# CONNECTOR.net
KiCad netlist of a schematic drawn in Altium Designer
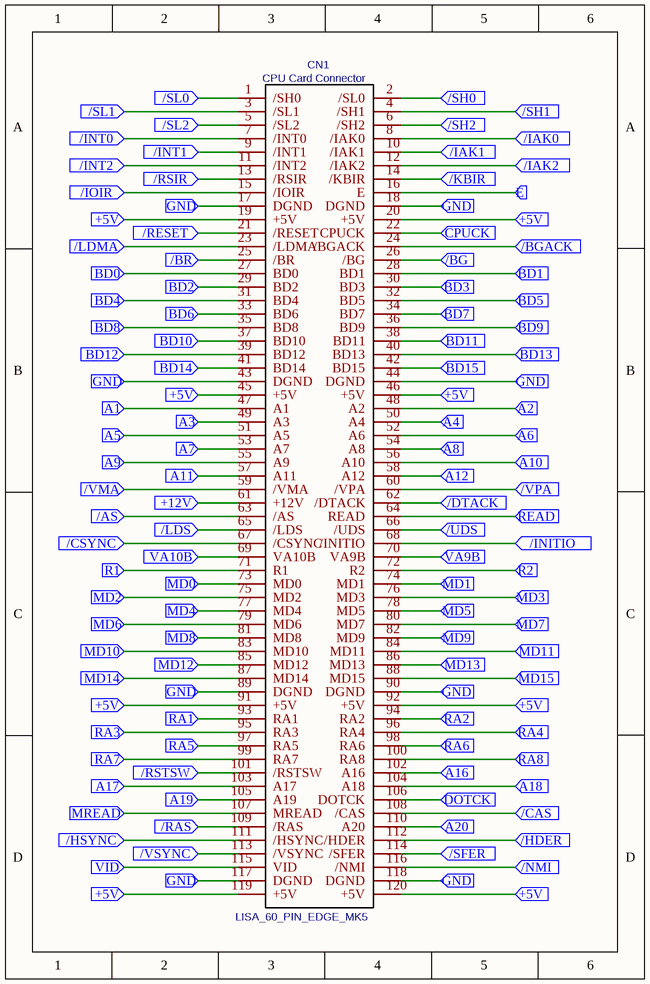
[diagram p0: CONNECTOR.schdoc]

(export (version "E")
  (design (tool "Eeschema 10.0.6"))
  (components
    (comp (ref "CN1")
      (value "CPU Card Connector")
      (fields (field (name "CONTRIBUTOR") "will_tooker"))
      (libsource (lib "altium-import") (part "root_0_CPU Card Connector_"))
    )
  )
  (nets
    (net (code "1") (name "/+5V") (class "Default")
      (node (ref "CN1") (pin "119") (pinfunction "+5V_119") (pintype "passive"))
      (node (ref "CN1") (pin "120") (pinfunction "+5V_120") (pintype "passive"))
      (node (ref "CN1") (pin "19") (pinfunction "+5V_19") (pintype "passive"))
      (node (ref "CN1") (pin "20") (pinfunction "+5V_20") (pintype "passive"))
      (node (ref "CN1") (pin "45") (pinfunction "+5V_45") (pintype "passive"))
      (node (ref "CN1") (pin "46") (pinfunction "+5V_46") (pintype "passive"))
      (node (ref "CN1") (pin "91") (pinfunction "+5V_91") (pintype "passive"))
      (node (ref "CN1") (pin "92") (pinfunction "+5V_92") (pintype "passive"))
    )
    (net (code "2") (name "/+12V") (class "Default")
      (node (ref "CN1") (pin "61") (pinfunction "+12V_61") (pintype "passive"))
    )
    (net (code "3") (name "/A1") (class "Default")
      (node (ref "CN1") (pin "47") (pinfunction "A1_47") (pintype "passive"))
    )
    (net (code "4") (name "/A2") (class "Default")
      (node (ref "CN1") (pin "48") (pinfunction "A2_48") (pintype "passive"))
    )
    (net (code "5") (name "/A3") (class "Default")
      (node (ref "CN1") (pin "49") (pinfunction "A3_49") (pintype "passive"))
    )
    (net (code "6") (name "/A4") (class "Default")
      (node (ref "CN1") (pin "50") (pinfunction "A4_50") (pintype "passive"))
    )
    (net (code "7") (name "/A5") (class "Default")
      (node (ref "CN1") (pin "51") (pinfunction "A5_51") (pintype "passive"))
    )
    (net (code "8") (name "/A6") (class "Default")
      (node (ref "CN1") (pin "52") (pinfunction "A6_52") (pintype "passive"))
    )
    (net (code "9") (name "/A7") (class "Default")
      (node (ref "CN1") (pin "53") (pinfunction "A7_53") (pintype "passive"))
    )
    (net (code "10") (name "/A8") (class "Default")
      (node (ref "CN1") (pin "54") (pinfunction "A8_54") (pintype "passive"))
    )
    (net (code "11") (name "/A9") (class "Default")
      (node (ref "CN1") (pin "55") (pinfunction "A9_55") (pintype "passive"))
    )
    (net (code "12") (name "/A10") (class "Default")
      (node (ref "CN1") (pin "56") (pinfunction "A10_56") (pintype "passive"))
    )
    (net (code "13") (name "/A11") (class "Default")
      (node (ref "CN1") (pin "57") (pinfunction "A11_57") (pintype "passive"))
    )
    (net (code "14") (name "/A12") (class "Default")
      (node (ref "CN1") (pin "58") (pinfunction "A12_58") (pintype "passive"))
    )
    (net (code "15") (name "/A16") (class "Default")
      (node (ref "CN1") (pin "102") (pinfunction "A16_102") (pintype "passive"))
    )
    (net (code "16") (name "/A17") (class "Default")
      (node (ref "CN1") (pin "103") (pinfunction "A17_103") (pintype "passive"))
    )
    (net (code "17") (name "/A18") (class "Default")
      (node (ref "CN1") (pin "104") (pinfunction "A18_104") (pintype "passive"))
    )
    (net (code "18") (name "/A19") (class "Default")
      (node (ref "CN1") (pin "105") (pinfunction "A19_105") (pintype "passive"))
    )
    (net (code "19") (name "/A20") (class "Default")
      (node (ref "CN1") (pin "110") (pinfunction "A20_110") (pintype "passive"))
    )
    (net (code "20") (name "/BD0") (class "Default")
      (node (ref "CN1") (pin "27") (pinfunction "BD0_27") (pintype "passive"))
    )
    (net (code "21") (name "/BD1") (class "Default")
      (node (ref "CN1") (pin "28") (pinfunction "BD1_28") (pintype "passive"))
    )
    (net (code "22") (name "/BD2") (class "Default")
      (node (ref "CN1") (pin "29") (pinfunction "BD2_29") (pintype "passive"))
    )
    (net (code "23") (name "/BD3") (class "Default")
      (node (ref "CN1") (pin "30") (pinfunction "BD3_30") (pintype "passive"))
    )
    (net (code "24") (name "/BD4") (class "Default")
      (node (ref "CN1") (pin "31") (pinfunction "BD4_31") (pintype "passive"))
    )
    (net (code "25") (name "/BD5") (class "Default")
      (node (ref "CN1") (pin "32") (pinfunction "BD5_32") (pintype "passive"))
    )
    (net (code "26") (name "/BD6") (class "Default")
      (node (ref "CN1") (pin "33") (pinfunction "BD6_33") (pintype "passive"))
    )
    (net (code "27") (name "/BD7") (class "Default")
      (node (ref "CN1") (pin "34") (pinfunction "BD7_34") (pintype "passive"))
    )
    (net (code "28") (name "/BD8") (class "Default")
      (node (ref "CN1") (pin "35") (pinfunction "BD8_35") (pintype "passive"))
    )
    (net (code "29") (name "/BD9") (class "Default")
      (node (ref "CN1") (pin "36") (pinfunction "BD9_36") (pintype "passive"))
    )
    (net (code "30") (name "/BD10") (class "Default")
      (node (ref "CN1") (pin "37") (pinfunction "BD10_37") (pintype "passive"))
    )
    (net (code "31") (name "/BD11") (class "Default")
      (node (ref "CN1") (pin "38") (pinfunction "BD11_38") (pintype "passive"))
    )
    (net (code "32") (name "/BD12") (class "Default")
      (node (ref "CN1") (pin "39") (pinfunction "BD12_39") (pintype "passive"))
    )
    (net (code "33") (name "/BD13") (class "Default")
      (node (ref "CN1") (pin "40") (pinfunction "BD13_40") (pintype "passive"))
    )
    (net (code "34") (name "/BD14") (class "Default")
      (node (ref "CN1") (pin "41") (pinfunction "BD14_41") (pintype "passive"))
    )
    (net (code "35") (name "/BD15") (class "Default")
      (node (ref "CN1") (pin "42") (pinfunction "BD15_42") (pintype "passive"))
    )
    (net (code "36") (name "/CPUCK") (class "Default")
      (node (ref "CN1") (pin "22") (pinfunction "CPUCK_22") (pintype "passive"))
    )
    (net (code "37") (name "/DOTCK") (class "Default")
      (node (ref "CN1") (pin "106") (pinfunction "DOTCK_106") (pintype "passive"))
    )
    (net (code "38") (name "/E") (class "Default")
      (node (ref "CN1") (pin "16") (pinfunction "E_16") (pintype "passive"))
    )
    (net (code "39") (name "/GND") (class "Default")
      (node (ref "CN1") (pin "117") (pinfunction "DGND_117") (pintype "passive"))
      (node (ref "CN1") (pin "118") (pinfunction "DGND_118") (pintype "passive"))
      (node (ref "CN1") (pin "17") (pinfunction "DGND_17") (pintype "passive"))
      (node (ref "CN1") (pin "18") (pinfunction "DGND_18") (pintype "passive"))
      (node (ref "CN1") (pin "43") (pinfunction "DGND_43") (pintype "passive"))
      (node (ref "CN1") (pin "44") (pinfunction "DGND_44") (pintype "passive"))
      (node (ref "CN1") (pin "89") (pinfunction "DGND_89") (pintype "passive"))
      (node (ref "CN1") (pin "90") (pinfunction "DGND_90") (pintype "passive"))
    )
    (net (code "40") (name "/MD0") (class "Default")
      (node (ref "CN1") (pin "73") (pinfunction "MD0_73") (pintype "passive"))
    )
    (net (code "41") (name "/MD1") (class "Default")
      (node (ref "CN1") (pin "74") (pinfunction "MD1_74") (pintype "passive"))
    )
    (net (code "42") (name "/MD2") (class "Default")
      (node (ref "CN1") (pin "75") (pinfunction "MD2_75") (pintype "passive"))
    )
    (net (code "43") (name "/MD3") (class "Default")
      (node (ref "CN1") (pin "76") (pinfunction "MD3_76") (pintype "passive"))
    )
    (net (code "44") (name "/MD4") (class "Default")
      (node (ref "CN1") (pin "77") (pinfunction "MD4_77") (pintype "passive"))
    )
    (net (code "45") (name "/MD5") (class "Default")
      (node (ref "CN1") (pin "78") (pinfunction "MD5_78") (pintype "passive"))
    )
    (net (code "46") (name "/MD6") (class "Default")
      (node (ref "CN1") (pin "79") (pinfunction "MD6_79") (pintype "passive"))
    )
    (net (code "47") (name "/MD7") (class "Default")
      (node (ref "CN1") (pin "80") (pinfunction "MD7_80") (pintype "passive"))
    )
    (net (code "48") (name "/MD8") (class "Default")
      (node (ref "CN1") (pin "81") (pinfunction "MD8_81") (pintype "passive"))
    )
    (net (code "49") (name "/MD9") (class "Default")
      (node (ref "CN1") (pin "82") (pinfunction "MD9_82") (pintype "passive"))
    )
    (net (code "50") (name "/MD10") (class "Default")
      (node (ref "CN1") (pin "83") (pinfunction "MD10_83") (pintype "passive"))
    )
    (net (code "51") (name "/MD11") (class "Default")
      (node (ref "CN1") (pin "84") (pinfunction "MD11_84") (pintype "passive"))
    )
    (net (code "52") (name "/MD12") (class "Default")
      (node (ref "CN1") (pin "85") (pinfunction "MD12_85") (pintype "passive"))
    )
    (net (code "53") (name "/MD13") (class "Default")
      (node (ref "CN1") (pin "86") (pinfunction "MD13_86") (pintype "passive"))
    )
    (net (code "54") (name "/MD14") (class "Default")
      (node (ref "CN1") (pin "87") (pinfunction "MD14_87") (pintype "passive"))
    )
    (net (code "55") (name "/MD15") (class "Default")
      (node (ref "CN1") (pin "88") (pinfunction "MD15_88") (pintype "passive"))
    )
    (net (code "56") (name "/MREAD") (class "Default")
      (node (ref "CN1") (pin "107") (pinfunction "MREAD_107") (pintype "passive"))
    )
    (net (code "57") (name "/R1") (class "Default")
      (node (ref "CN1") (pin "71") (pinfunction "R1_71") (pintype "passive"))
    )
    (net (code "58") (name "/R2") (class "Default")
      (node (ref "CN1") (pin "72") (pinfunction "R2_72") (pintype "passive"))
    )
    (net (code "59") (name "/RA1") (class "Default")
      (node (ref "CN1") (pin "93") (pinfunction "RA1_93") (pintype "passive"))
    )
    (net (code "60") (name "/RA2") (class "Default")
      (node (ref "CN1") (pin "94") (pinfunction "RA2_94") (pintype "passive"))
    )
    (net (code "61") (name "/RA3") (class "Default")
      (node (ref "CN1") (pin "95") (pinfunction "RA3_95") (pintype "passive"))
    )
    (net (code "62") (name "/RA4") (class "Default")
      (node (ref "CN1") (pin "96") (pinfunction "RA4_96") (pintype "passive"))
    )
    (net (code "63") (name "/RA5") (class "Default")
      (node (ref "CN1") (pin "97") (pinfunction "RA5_97") (pintype "passive"))
    )
    (net (code "64") (name "/RA6") (class "Default")
      (node (ref "CN1") (pin "98") (pinfunction "RA6_98") (pintype "passive"))
    )
    (net (code "65") (name "/RA7") (class "Default")
      (node (ref "CN1") (pin "99") (pinfunction "RA7_99") (pintype "passive"))
    )
    (net (code "66") (name "/RA8") (class "Default")
      (node (ref "CN1") (pin "100") (pinfunction "RA8_100") (pintype "passive"))
    )
    (net (code "67") (name "/READ") (class "Default")
      (node (ref "CN1") (pin "64") (pinfunction "READ_64") (pintype "passive"))
    )
    (net (code "68") (name "/VA9B") (class "Default")
      (node (ref "CN1") (pin "70") (pinfunction "VA9B_70") (pintype "passive"))
    )
    (net (code "69") (name "/VA10B") (class "Default")
      (node (ref "CN1") (pin "69") (pinfunction "VA10B_69") (pintype "passive"))
    )
    (net (code "70") (name "/VID") (class "Default")
      (node (ref "CN1") (pin "115") (pinfunction "VID_115") (pintype "passive"))
    )
    (net (code "71") (name "/{slash}AS") (class "Default")
      (node (ref "CN1") (pin "63") (pinfunction "/AS_63") (pintype "passive"))
    )
    (net (code "72") (name "/{slash}BG") (class "Default")
      (node (ref "CN1") (pin "26") (pinfunction "/BG_26") (pintype "passive"))
    )
    (net (code "73") (name "/{slash}BGACK") (class "Default")
      (node (ref "CN1") (pin "24") (pinfunction "/BGACK_24") (pintype "passive"))
    )
    (net (code "74") (name "/{slash}BR") (class "Default")
      (node (ref "CN1") (pin "25") (pinfunction "/BR_25") (pintype "passive"))
    )
    (net (code "75") (name "/{slash}CAS") (class "Default")
      (node (ref "CN1") (pin "108") (pinfunction "/CAS_108") (pintype "passive"))
    )
    (net (code "76") (name "/{slash}CSYNC") (class "Default")
      (node (ref "CN1") (pin "67") (pinfunction "/CSYNC_67") (pintype "passive"))
    )
    (net (code "77") (name "/{slash}DTACK") (class "Default")
      (node (ref "CN1") (pin "62") (pinfunction "/DTACK_62") (pintype "passive"))
    )
    (net (code "78") (name "/{slash}HDER") (class "Default")
      (node (ref "CN1") (pin "112") (pinfunction "/HDER_112") (pintype "passive"))
    )
    (net (code "79") (name "/{slash}HSYNC") (class "Default")
      (node (ref "CN1") (pin "111") (pinfunction "/HSYNC_111") (pintype "passive"))
    )
    (net (code "80") (name "/{slash}IAK0") (class "Default")
      (node (ref "CN1") (pin "8") (pinfunction "/IAK0_8") (pintype "passive"))
    )
    (net (code "81") (name "/{slash}IAK1") (class "Default")
      (node (ref "CN1") (pin "10") (pinfunction "/IAK1_10") (pintype "passive"))
    )
    (net (code "82") (name "/{slash}IAK2") (class "Default")
      (node (ref "CN1") (pin "12") (pinfunction "/IAK2_12") (pintype "passive"))
    )
    (net (code "83") (name "/{slash}INITIO") (class "Default")
      (node (ref "CN1") (pin "68") (pinfunction "/INITIO_68") (pintype "passive"))
    )
    (net (code "84") (name "/{slash}INT0") (class "Default")
      (node (ref "CN1") (pin "7") (pinfunction "/INT0_7") (pintype "passive"))
    )
    (net (code "85") (name "/{slash}INT1") (class "Default")
      (node (ref "CN1") (pin "9") (pinfunction "/INT1_9") (pintype "passive"))
    )
    (net (code "86") (name "/{slash}INT2") (class "Default")
      (node (ref "CN1") (pin "11") (pinfunction "/INT2_11") (pintype "passive"))
    )
    (net (code "87") (name "/{slash}IOIR") (class "Default")
      (node (ref "CN1") (pin "15") (pinfunction "/IOIR_15") (pintype "passive"))
    )
    (net (code "88") (name "/{slash}KBIR") (class "Default")
      (node (ref "CN1") (pin "14") (pinfunction "/KBIR_14") (pintype "passive"))
    )
    (net (code "89") (name "/{slash}LDMA") (class "Default")
      (node (ref "CN1") (pin "23") (pinfunction "/LDMA_23") (pintype "passive"))
    )
    (net (code "90") (name "/{slash}LDS") (class "Default")
      (node (ref "CN1") (pin "65") (pinfunction "/LDS_65") (pintype "passive"))
    )
    (net (code "91") (name "/{slash}NMI") (class "Default")
      (node (ref "CN1") (pin "116") (pinfunction "/NMI_116") (pintype "passive"))
    )
    (net (code "92") (name "/{slash}RAS") (class "Default")
      (node (ref "CN1") (pin "109") (pinfunction "/RAS_109") (pintype "passive"))
    )
    (net (code "93") (name "/{slash}RESET") (class "Default")
      (node (ref "CN1") (pin "21") (pinfunction "/RESET_21") (pintype "passive"))
    )
    (net (code "94") (name "/{slash}RSIR") (class "Default")
      (node (ref "CN1") (pin "13") (pinfunction "/RSIR_13") (pintype "passive"))
    )
    (net (code "95") (name "/{slash}RSTSW") (class "Default")
      (node (ref "CN1") (pin "101") (pinfunction "/RSTSW_101") (pintype "passive"))
    )
    (net (code "96") (name "/{slash}SFER") (class "Default")
      (node (ref "CN1") (pin "114") (pinfunction "/SFER_114") (pintype "passive"))
    )
    (net (code "97") (name "/{slash}SH0") (class "Default")
      (node (ref "CN1") (pin "2") (pinfunction "/SL0_2") (pintype "passive"))
    )
    (net (code "98") (name "/{slash}SH1") (class "Default")
      (node (ref "CN1") (pin "4") (pinfunction "/SH1_4") (pintype "passive"))
    )
    (net (code "99") (name "/{slash}SH2") (class "Default")
      (node (ref "CN1") (pin "6") (pinfunction "/SH2_6") (pintype "passive"))
    )
    (net (code "100") (name "/{slash}SL0") (class "Default")
      (node (ref "CN1") (pin "1") (pinfunction "/SH0_1") (pintype "passive"))
    )
    (net (code "101") (name "/{slash}SL1") (class "Default")
      (node (ref "CN1") (pin "3") (pinfunction "/SL1_3") (pintype "passive"))
    )
    (net (code "102") (name "/{slash}SL2") (class "Default")
      (node (ref "CN1") (pin "5") (pinfunction "/SL2_5") (pintype "passive"))
    )
    (net (code "103") (name "/{slash}UDS") (class "Default")
      (node (ref "CN1") (pin "66") (pinfunction "/UDS_66") (pintype "passive"))
    )
    (net (code "104") (name "/{slash}VMA") (class "Default")
      (node (ref "CN1") (pin "59") (pinfunction "/VMA_59") (pintype "passive"))
    )
    (net (code "105") (name "/{slash}VPA") (class "Default")
      (node (ref "CN1") (pin "60") (pinfunction "/VPA_60") (pintype "passive"))
    )
    (net (code "106") (name "/{slash}VSYNC") (class "Default")
      (node (ref "CN1") (pin "113") (pinfunction "/VSYNC_113") (pintype "passive"))
    )
  )
)
